# PDM-S09-V00-HarnessConnector.net
KiCad netlist of a schematic drawn in Altium Designer
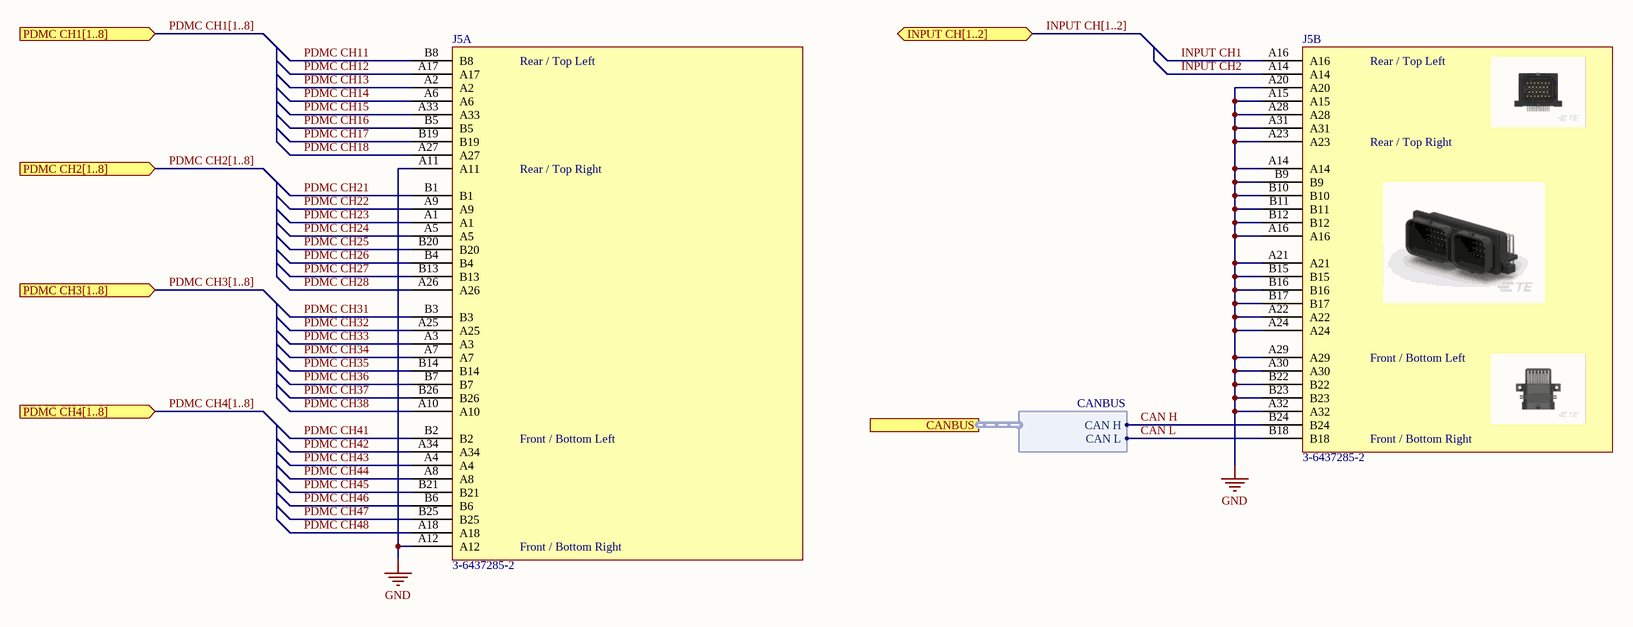
[diagram p0: PDM-S09-V00-HarnessConnector.SchDoc]

(export (version "E")
  (design (tool "Eeschema 10.0.6"))
  (components
    (comp (ref "J5")
      (value "3-6437285-2")
      (footprint "SUPER SEAL RIGHT 60POS")
      (description "Connector Header Through Hole, Right Angle 60 position 0.118\" (3.00mm), 1.00mm contacts")
      (libsource (lib "") (part "3-6437285-2_1"))
    )
  )
  (nets
    (net (code "2") (name "/CAN H") (class "Default")
      (node (ref "J5") (pin "B24") (pinfunction "B24_B24") (pintype "passive"))
    )
    (net (code "3") (name "/CAN L") (class "Default")
      (node (ref "J5") (pin "B18") (pinfunction "B18_B18") (pintype "passive"))
    )
    (net (code "4") (name "/INPUT CH1") (class "Default")
      (node (ref "J5") (pin "A16") (pinfunction "A16_A16") (pintype "passive"))
    )
    (net (code "5") (name "/INPUT CH2") (class "Default")
      (node (ref "J5") (pin "A14") (pinfunction "A14_A14") (pintype "passive"))
    )
    (net (code "6") (name "/PDMC CH11") (class "Default")
      (node (ref "J5") (pin "B8") (pinfunction "B8_B8") (pintype "passive"))
    )
    (net (code "7") (name "/PDMC CH12") (class "Default")
      (node (ref "J5") (pin "A17") (pinfunction "A17_A17") (pintype "passive"))
    )
    (net (code "8") (name "/PDMC CH13") (class "Default")
      (node (ref "J5") (pin "A2") (pinfunction "A2_A2") (pintype "passive"))
    )
    (net (code "9") (name "/PDMC CH14") (class "Default")
      (node (ref "J5") (pin "A6") (pinfunction "A6_A6") (pintype "passive"))
    )
    (net (code "10") (name "/PDMC CH15") (class "Default")
      (node (ref "J5") (pin "A33") (pinfunction "A33_A33") (pintype "passive"))
    )
    (net (code "11") (name "/PDMC CH16") (class "Default")
      (node (ref "J5") (pin "B5") (pinfunction "B5_B5") (pintype "passive"))
    )
    (net (code "12") (name "/PDMC CH17") (class "Default")
      (node (ref "J5") (pin "B19") (pinfunction "B19_B19") (pintype "passive"))
    )
    (net (code "13") (name "/PDMC CH18") (class "Default")
      (node (ref "J5") (pin "A27") (pinfunction "A27_A27") (pintype "passive"))
    )
    (net (code "14") (name "/PDMC CH21") (class "Default")
      (node (ref "J5") (pin "B1") (pinfunction "B1_B1") (pintype "passive"))
    )
    (net (code "15") (name "/PDMC CH22") (class "Default")
      (node (ref "J5") (pin "A9") (pinfunction "A9_A9") (pintype "passive"))
    )
    (net (code "16") (name "/PDMC CH23") (class "Default")
      (node (ref "J5") (pin "A1") (pinfunction "A1_A1") (pintype "passive"))
    )
    (net (code "17") (name "/PDMC CH24") (class "Default")
      (node (ref "J5") (pin "A5") (pinfunction "A5_A5") (pintype "passive"))
    )
    (net (code "18") (name "/PDMC CH25") (class "Default")
      (node (ref "J5") (pin "B20") (pinfunction "B20_B20") (pintype "passive"))
    )
    (net (code "19") (name "/PDMC CH26") (class "Default")
      (node (ref "J5") (pin "B4") (pinfunction "B4_B4") (pintype "passive"))
    )
    (net (code "20") (name "/PDMC CH27") (class "Default")
      (node (ref "J5") (pin "B13") (pinfunction "B13_B13") (pintype "passive"))
    )
    (net (code "21") (name "/PDMC CH28") (class "Default")
      (node (ref "J5") (pin "A26") (pinfunction "A26_A26") (pintype "passive"))
    )
    (net (code "22") (name "/PDMC CH31") (class "Default")
      (node (ref "J5") (pin "B3") (pinfunction "B3_B3") (pintype "passive"))
    )
    (net (code "23") (name "/PDMC CH32") (class "Default")
      (node (ref "J5") (pin "A25") (pinfunction "A25_A25") (pintype "passive"))
    )
    (net (code "24") (name "/PDMC CH33") (class "Default")
      (node (ref "J5") (pin "A3") (pinfunction "A3_A3") (pintype "passive"))
    )
    (net (code "25") (name "/PDMC CH34") (class "Default")
      (node (ref "J5") (pin "A7") (pinfunction "A7_A7") (pintype "passive"))
    )
    (net (code "26") (name "/PDMC CH35") (class "Default")
      (node (ref "J5") (pin "B14") (pinfunction "B14_B14") (pintype "passive"))
    )
    (net (code "27") (name "/PDMC CH36") (class "Default")
      (node (ref "J5") (pin "B7") (pinfunction "B7_B7") (pintype "passive"))
    )
    (net (code "28") (name "/PDMC CH37") (class "Default")
      (node (ref "J5") (pin "B26") (pinfunction "B26_B26") (pintype "passive"))
    )
    (net (code "29") (name "/PDMC CH38") (class "Default")
      (node (ref "J5") (pin "A10") (pinfunction "A10_A10") (pintype "passive"))
    )
    (net (code "30") (name "/PDMC CH41") (class "Default")
      (node (ref "J5") (pin "B2") (pinfunction "B2_B2") (pintype "passive"))
    )
    (net (code "31") (name "/PDMC CH42") (class "Default")
      (node (ref "J5") (pin "A34") (pinfunction "A34_A34") (pintype "passive"))
    )
    (net (code "32") (name "/PDMC CH43") (class "Default")
      (node (ref "J5") (pin "A4") (pinfunction "A4_A4") (pintype "passive"))
    )
    (net (code "33") (name "/PDMC CH44") (class "Default")
      (node (ref "J5") (pin "A8") (pinfunction "A8_A8") (pintype "passive"))
    )
    (net (code "34") (name "/PDMC CH45") (class "Default")
      (node (ref "J5") (pin "B21") (pinfunction "B21_B21") (pintype "passive"))
    )
    (net (code "35") (name "/PDMC CH46") (class "Default")
      (node (ref "J5") (pin "B6") (pinfunction "B6_B6") (pintype "passive"))
    )
    (net (code "36") (name "/PDMC CH47") (class "Default")
      (node (ref "J5") (pin "B25") (pinfunction "B25_B25") (pintype "passive"))
    )
    (net (code "37") (name "/PDMC CH48") (class "Default")
      (node (ref "J5") (pin "A18") (pinfunction "A18_A18") (pintype "passive"))
    )
    (net (code "44") (name "GND") (class "Default")
      (node (ref "J5") (pin "A11") (pinfunction "A11_A11") (pintype "passive"))
      (node (ref "J5") (pin "A12") (pinfunction "A12_A12") (pintype "passive"))
      (node (ref "J5") (pin "A14") (pinfunction "A14_A14") (pintype "passive"))
      (node (ref "J5") (pin "A15") (pinfunction "A15_A15") (pintype "passive"))
      (node (ref "J5") (pin "A16") (pinfunction "A16_A16") (pintype "passive"))
      (node (ref "J5") (pin "A20") (pinfunction "A20_A20") (pintype "passive"))
      (node (ref "J5") (pin "A21") (pinfunction "A21_A21") (pintype "passive"))
      (node (ref "J5") (pin "A22") (pinfunction "A22_A22") (pintype "passive"))
      (node (ref "J5") (pin "A23") (pinfunction "A23_A23") (pintype "passive"))
      (node (ref "J5") (pin "A24") (pinfunction "A24_A24") (pintype "passive"))
      (node (ref "J5") (pin "A28") (pinfunction "A28_A28") (pintype "passive"))
      (node (ref "J5") (pin "A29") (pinfunction "A29_A29") (pintype "passive"))
      (node (ref "J5") (pin "A30") (pinfunction "A30_A30") (pintype "passive"))
      (node (ref "J5") (pin "A31") (pinfunction "A31_A31") (pintype "passive"))
      (node (ref "J5") (pin "A32") (pinfunction "A32_A32") (pintype "passive"))
      (node (ref "J5") (pin "B10") (pinfunction "B10_B10") (pintype "passive"))
      (node (ref "J5") (pin "B11") (pinfunction "B11_B11") (pintype "passive"))
      (node (ref "J5") (pin "B12") (pinfunction "B12_B12") (pintype "passive"))
      (node (ref "J5") (pin "B15") (pinfunction "B15_B15") (pintype "passive"))
      (node (ref "J5") (pin "B16") (pinfunction "B16_B16") (pintype "passive"))
      (node (ref "J5") (pin "B17") (pinfunction "B17_B17") (pintype "passive"))
      (node (ref "J5") (pin "B22") (pinfunction "B22_B22") (pintype "passive"))
      (node (ref "J5") (pin "B23") (pinfunction "B23_B23") (pintype "passive"))
      (node (ref "J5") (pin "B9") (pinfunction "B9_B9") (pintype "passive"))
    )
  )
)
